# QwiicHUDs9.net
KiCad netlist of a schematic drawn in EAGLE
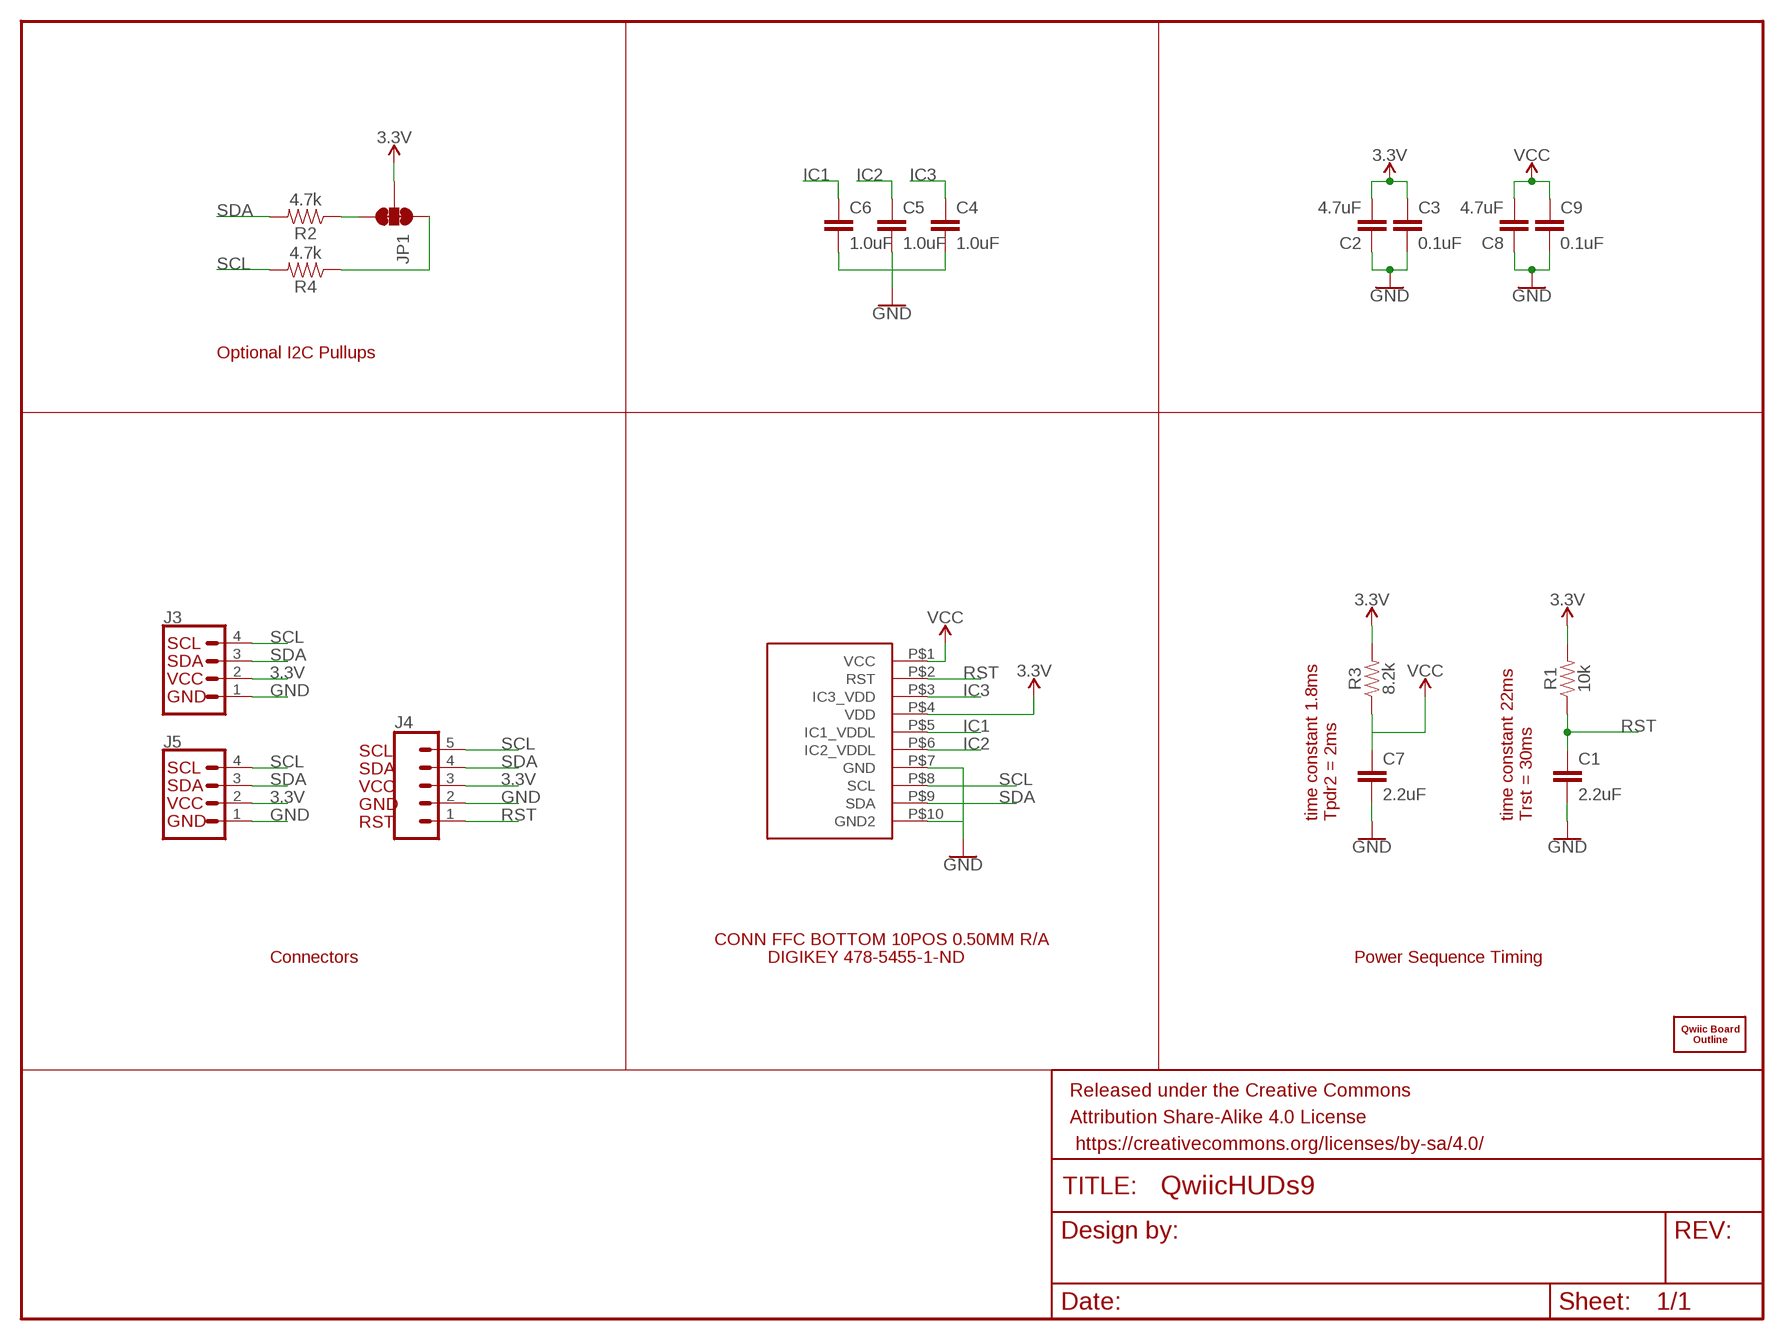
[diagram p0: schematic, sheet 1]

(export (version "E")
  (design (tool "Eeschema 10.0.6"))
  (components
    (comp (ref "C1")
      (value "2.2uF")
      (footprint "eagle-import:0603")
      (libsource (lib "eagle-import") (part "2.2UF-0603-10V-20%"))
    )
    (comp (ref "C2")
      (value "4.7uF")
      (footprint "eagle-import:0603")
      (libsource (lib "eagle-import") (part "4.7UF0603"))
    )
    (comp (ref "C3")
      (value "0.1uF")
      (footprint "eagle-import:0603")
      (libsource (lib "eagle-import") (part "0.1UF-0603-25V-5%"))
    )
    (comp (ref "C4")
      (value "1.0uF")
      (footprint "eagle-import:0603")
      (libsource (lib "eagle-import") (part "1.0UF-0603-16V-10%"))
    )
    (comp (ref "C5")
      (value "1.0uF")
      (footprint "eagle-import:0603")
      (libsource (lib "eagle-import") (part "1.0UF-0603-16V-10%"))
    )
    (comp (ref "C6")
      (value "1.0uF")
      (footprint "eagle-import:0603")
      (libsource (lib "eagle-import") (part "1.0UF-0603-16V-10%"))
    )
    (comp (ref "C7")
      (value "2.2uF")
      (footprint "eagle-import:0603")
      (libsource (lib "eagle-import") (part "2.2UF-0603-10V-20%"))
    )
    (comp (ref "C8")
      (value "4.7uF")
      (footprint "eagle-import:0603")
      (libsource (lib "eagle-import") (part "4.7UF0603"))
    )
    (comp (ref "C9")
      (value "0.1uF")
      (footprint "eagle-import:0603")
      (libsource (lib "eagle-import") (part "0.1UF-0603-25V-5%"))
    )
    (comp (ref "FRAME1")
      (value "FRAME-LETTER")
      (footprint "eagle-import:CREATIVE_COMMONS")
      (libsource (lib "eagle-import") (part "FRAME-LETTER"))
    )
    (comp (ref "J3")
      (value "I2C_STANDARDJS-1MM")
      (footprint "eagle-import:1X04_1MM_RA")
      (libsource (lib "eagle-import") (part "I2C_STANDARDJS-1MM"))
    )
    (comp (ref "J4")
      (value "CONN_05")
      (footprint "eagle-import:1X05")
      (libsource (lib "eagle-import") (part "CONN_05"))
    )
    (comp (ref "J5")
      (value "I2C_STANDARDJS-1MM")
      (footprint "eagle-import:1X04_1MM_RA")
      (libsource (lib "eagle-import") (part "I2C_STANDARDJS-1MM"))
    )
    (comp (ref "JP1")
      (value "JUMPER-SMT_3_2-NC_TRACE_SILK")
      (footprint "eagle-import:SMT-JUMPER_3_2-NC_TRACE_SILK")
      (libsource (lib "eagle-import") (part "JUMPER-SMT_3_2-NC_TRACE_SILK"))
    )
    (comp (ref "R1")
      (value "10k")
      (footprint "eagle-import:0603")
      (libsource (lib "eagle-import") (part "10KOHM-0603-1/10W-1%"))
    )
    (comp (ref "R2")
      (value "4.7k")
      (footprint "eagle-import:0603")
      (libsource (lib "eagle-import") (part "4.7KOHM-0603-1/10W-1%"))
    )
    (comp (ref "R3")
      (value "8.2k")
      (footprint "eagle-import:0603")
      (libsource (lib "eagle-import") (part "8.2KOHM-0603-1/10W-5%"))
    )
    (comp (ref "R4")
      (value "4.7k")
      (footprint "eagle-import:0603")
      (libsource (lib "eagle-import") (part "4.7KOHM-0603-1/10W-1%"))
    )
    (comp (ref "U$1")
      (value "WISECHIP_HUD_FPC")
      (footprint "eagle-import:SERIES6288")
      (libsource (lib "eagle-import") (part "WISECHIP_HUD_FPC"))
    )
    (comp (ref "U$2")
      (value "QWIIC_BOARD_OUTLINEH")
      (footprint "eagle-import:QWIIC_BOARD_MOUNT_HOLES")
      (libsource (lib "eagle-import") (part "QWIIC_BOARD_OUTLINEH"))
    )
  )
  (nets
    (net (code "1") (name "/IC1") (class "Default")
      (node (ref "C6") (pin "1") (pinfunction "1_1") (pintype "passive"))
      (node (ref "U$1") (pin "P$5") (pinfunction "IC1_VDDL_P$5") (pintype "bidirectional"))
    )
    (net (code "2") (name "/IC2") (class "Default")
      (node (ref "C5") (pin "1") (pinfunction "1_1") (pintype "passive"))
      (node (ref "U$1") (pin "P$6") (pinfunction "IC2_VDDL_P$6") (pintype "bidirectional"))
    )
    (net (code "3") (name "/IC3") (class "Default")
      (node (ref "C4") (pin "1") (pinfunction "1_1") (pintype "passive"))
      (node (ref "U$1") (pin "P$3") (pinfunction "IC3_VDD_P$3") (pintype "bidirectional"))
    )
    (net (code "4") (name "/RST") (class "Default")
      (node (ref "C1") (pin "1") (pinfunction "1_1") (pintype "passive"))
      (node (ref "J4") (pin "1") (pinfunction "1_1") (pintype "passive"))
      (node (ref "R1") (pin "1") (pinfunction "1_1") (pintype "passive"))
      (node (ref "U$1") (pin "P$2") (pinfunction "RST_P$2") (pintype "bidirectional"))
    )
    (net (code "5") (name "/SCL") (class "Default")
      (node (ref "J3") (pin "4") (pinfunction "SCL_4") (pintype "passive"))
      (node (ref "J4") (pin "5") (pinfunction "5_5") (pintype "passive"))
      (node (ref "J5") (pin "4") (pinfunction "SCL_4") (pintype "passive"))
      (node (ref "R4") (pin "2") (pinfunction "2_2") (pintype "passive"))
      (node (ref "U$1") (pin "P$8") (pinfunction "SCL_P$8") (pintype "bidirectional"))
    )
    (net (code "6") (name "/SDA") (class "Default")
      (node (ref "J3") (pin "3") (pinfunction "SDA_3") (pintype "passive"))
      (node (ref "J4") (pin "4") (pinfunction "4_4") (pintype "passive"))
      (node (ref "J5") (pin "3") (pinfunction "SDA_3") (pintype "passive"))
      (node (ref "R2") (pin "2") (pinfunction "2_2") (pintype "passive"))
      (node (ref "U$1") (pin "P$9") (pinfunction "SDA_P$9") (pintype "bidirectional"))
    )
    (net (code "7") (name "3.3V") (class "Default")
      (node (ref "C2") (pin "2") (pinfunction "2_2") (pintype "passive"))
      (node (ref "C3") (pin "1") (pinfunction "1_1") (pintype "passive"))
      (node (ref "J3") (pin "2") (pinfunction "VCC_2") (pintype "power_in"))
      (node (ref "J4") (pin "3") (pinfunction "3_3") (pintype "passive"))
      (node (ref "J5") (pin "2") (pinfunction "VCC_2") (pintype "power_in"))
      (node (ref "JP1") (pin "2") (pinfunction "2_2") (pintype "passive"))
      (node (ref "R1") (pin "2") (pinfunction "2_2") (pintype "passive"))
      (node (ref "R3") (pin "2") (pinfunction "2_2") (pintype "passive"))
      (node (ref "U$1") (pin "P$4") (pinfunction "VDD_P$4") (pintype "bidirectional"))
    )
    (net (code "8") (name "GND") (class "Default")
      (node (ref "C1") (pin "2") (pinfunction "2_2") (pintype "passive"))
      (node (ref "C2") (pin "1") (pinfunction "1_1") (pintype "passive"))
      (node (ref "C3") (pin "2") (pinfunction "2_2") (pintype "passive"))
      (node (ref "C4") (pin "2") (pinfunction "2_2") (pintype "passive"))
      (node (ref "C5") (pin "2") (pinfunction "2_2") (pintype "passive"))
      (node (ref "C6") (pin "2") (pinfunction "2_2") (pintype "passive"))
      (node (ref "C7") (pin "2") (pinfunction "2_2") (pintype "passive"))
      (node (ref "C8") (pin "1") (pinfunction "1_1") (pintype "passive"))
      (node (ref "C9") (pin "2") (pinfunction "2_2") (pintype "passive"))
      (node (ref "J3") (pin "1") (pinfunction "GND_1") (pintype "power_in"))
      (node (ref "J4") (pin "2") (pinfunction "2_2") (pintype "passive"))
      (node (ref "J5") (pin "1") (pinfunction "GND_1") (pintype "power_in"))
      (node (ref "U$1") (pin "P$10") (pinfunction "GND2_P$10") (pintype "bidirectional"))
      (node (ref "U$1") (pin "P$7") (pinfunction "GND_P$7") (pintype "bidirectional"))
    )
    (net (code "9") (name "Net-(JP1-Pad1)") (class "Default")
      (node (ref "JP1") (pin "1") (pinfunction "1_1") (pintype "passive"))
      (node (ref "R4") (pin "1") (pinfunction "1_1") (pintype "passive"))
    )
    (net (code "10") (name "Net-(JP1-Pad3)") (class "Default")
      (node (ref "JP1") (pin "3") (pinfunction "3_3") (pintype "passive"))
      (node (ref "R2") (pin "1") (pinfunction "1_1") (pintype "passive"))
    )
    (net (code "11") (name "VCC") (class "Default")
      (node (ref "C7") (pin "1") (pinfunction "1_1") (pintype "passive"))
      (node (ref "C8") (pin "2") (pinfunction "2_2") (pintype "passive"))
      (node (ref "C9") (pin "1") (pinfunction "1_1") (pintype "passive"))
      (node (ref "R3") (pin "1") (pinfunction "1_1") (pintype "passive"))
      (node (ref "U$1") (pin "P$1") (pinfunction "VCC_P$1") (pintype "bidirectional"))
    )
  )
)
